# power.net
KiCad netlist of a schematic drawn in Altium Designer
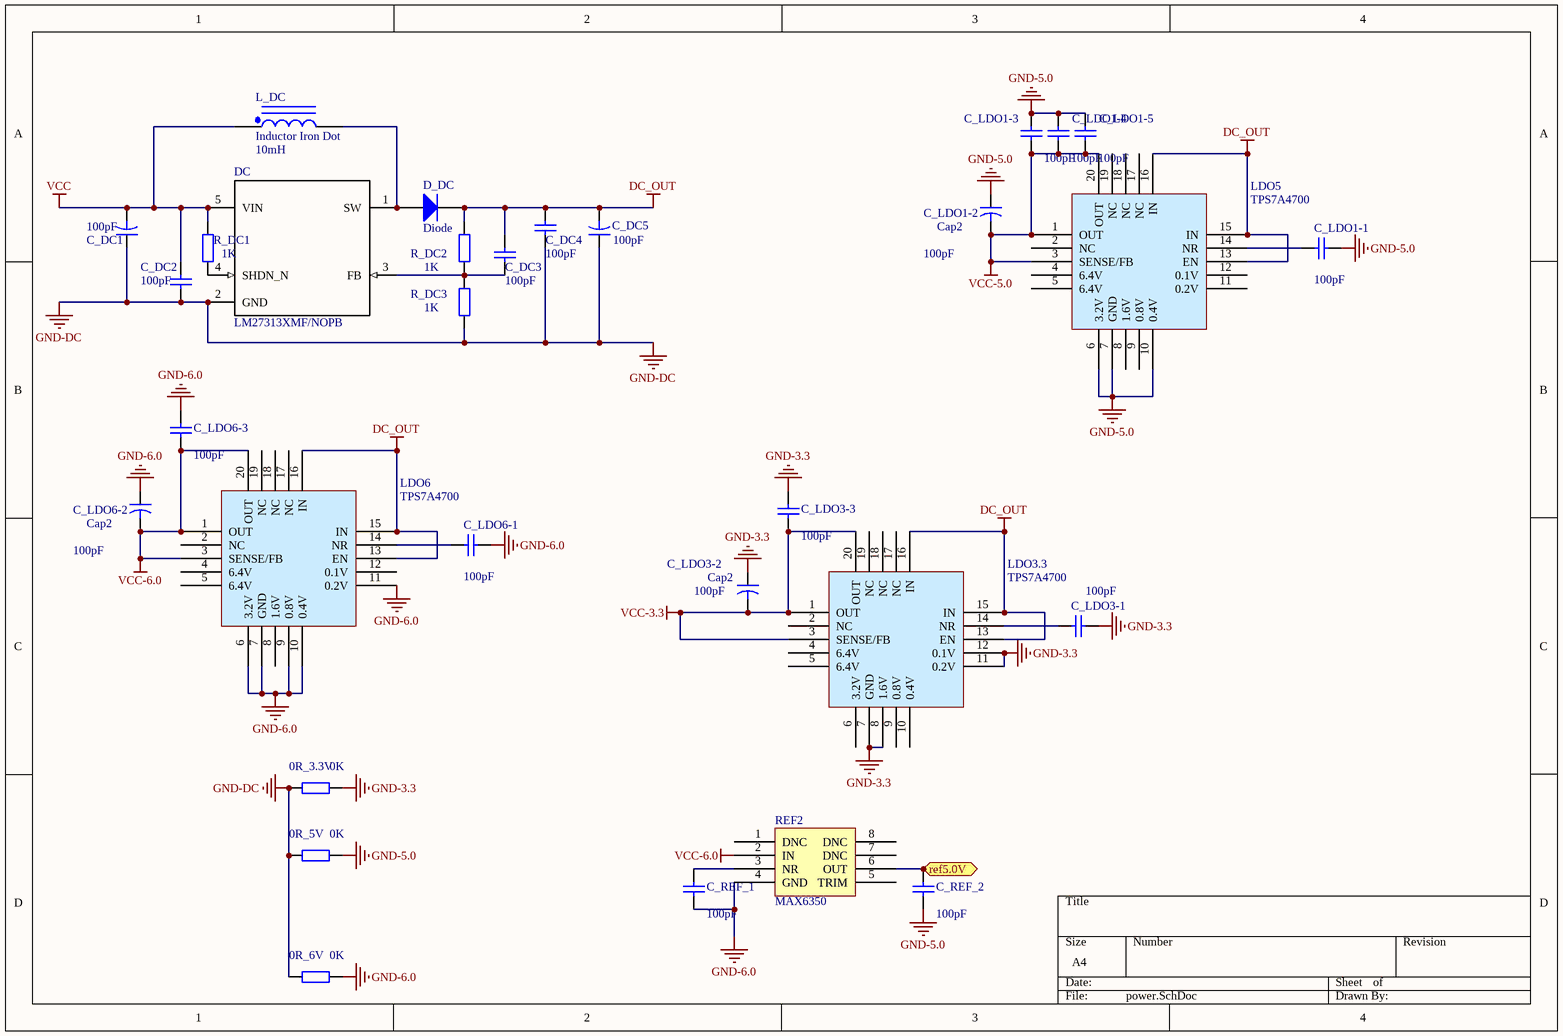
[diagram p0: power.SchDoc]

(export (version "E")
  (design (tool "Eeschema 10.0.6"))
  (components
    (comp (ref "0R_3.3V")
      (value "0K")
      (footprint "0603 - no")
      (description "Resistor")
      (fields (field (name "PUBLISHER") "Altium Limited"))
      (libsource (lib "") (part "Res2_1"))
    )
    (comp (ref "0R_5V")
      (value "0K")
      (footprint "0603 - no")
      (description "Resistor")
      (fields (field (name "PUBLISHER") "Altium Limited"))
      (libsource (lib "") (part "Res2_1"))
    )
    (comp (ref "0R_6V")
      (value "0K")
      (footprint "0603 - no")
      (description "Resistor")
      (fields (field (name "PUBLISHER") "Altium Limited"))
      (libsource (lib "") (part "Res2_1"))
    )
    (comp (ref "C_DC1")
      (value "100pF")
      (footprint "1210")
      (description "Capacitor")
      (fields (field (name "PUBLISHER") "Altium Limited"))
      (libsource (lib "Miscellaneous Devices") (part "Cap2"))
    )
    (comp (ref "C_DC2")
      (value "100pF")
      (footprint "0603 - no")
      (description "Capacitor")
      (fields (field (name "PUBLISHER") "Altium Limited"))
      (libsource (lib "Miscellaneous Devices") (part "Cap"))
    )
    (comp (ref "C_DC3")
      (value "100pF")
      (footprint "0603 - no")
      (description "Capacitor")
      (fields (field (name "PUBLISHER") "Altium Limited"))
      (libsource (lib "Miscellaneous Devices") (part "Cap"))
    )
    (comp (ref "C_DC4")
      (value "100pF")
      (footprint "0805")
      (description "Capacitor")
      (fields (field (name "PUBLISHER") "Altium Limited"))
      (libsource (lib "Miscellaneous Devices") (part "Cap"))
    )
    (comp (ref "C_DC5")
      (value "100pF")
      (footprint "1210")
      (description "Capacitor")
      (fields (field (name "PUBLISHER") "Altium Limited"))
      (libsource (lib "Miscellaneous Devices") (part "Cap2"))
    )
    (comp (ref "C_LDO1-1")
      (value "100pF")
      (footprint "0603 - no")
      (description "Capacitor")
      (fields (field (name "PUBLISHER") "Altium Limited"))
      (libsource (lib "Miscellaneous Devices") (part "Cap"))
    )
    (comp (ref "C_LDO1-2")
      (value "Cap2")
      (footprint "1210")
      (description "Capacitor")
      (fields (field (name "ALTIUM_VALUE") "100pF") (field (name "PUBLISHER") "Altium Limited"))
      (libsource (lib "Miscellaneous Devices") (part "Cap2"))
    )
    (comp (ref "C_LDO1-3")
      (value "100pF")
      (footprint "0805")
      (description "Capacitor")
      (fields (field (name "PUBLISHER") "Altium Limited"))
      (libsource (lib "Miscellaneous Devices") (part "Cap"))
    )
    (comp (ref "C_LDO1-4")
      (value "100pF")
      (footprint "0805")
      (description "Capacitor")
      (fields (field (name "PUBLISHER") "Altium Limited"))
      (libsource (lib "Miscellaneous Devices") (part "Cap"))
    )
    (comp (ref "C_LDO1-5")
      (value "100pF")
      (footprint "0805")
      (description "Capacitor")
      (fields (field (name "PUBLISHER") "Altium Limited"))
      (libsource (lib "Miscellaneous Devices") (part "Cap"))
    )
    (comp (ref "C_LDO3-1")
      (value "100pF")
      (footprint "0603 - no")
      (description "Capacitor")
      (fields (field (name "PUBLISHER") "Altium Limited"))
      (libsource (lib "Miscellaneous Devices") (part "Cap"))
    )
    (comp (ref "C_LDO3-2")
      (value "Cap2")
      (footprint "1210")
      (description "Capacitor")
      (fields (field (name "ALTIUM_VALUE") "100pF") (field (name "PUBLISHER") "Altium Limited"))
      (libsource (lib "Miscellaneous Devices") (part "Cap2"))
    )
    (comp (ref "C_LDO3-3")
      (value "100pF")
      (footprint "0805")
      (description "Capacitor")
      (fields (field (name "PUBLISHER") "Altium Limited"))
      (libsource (lib "Miscellaneous Devices") (part "Cap"))
    )
    (comp (ref "C_LDO6-1")
      (value "100pF")
      (footprint "0603 - no")
      (description "Capacitor")
      (fields (field (name "PUBLISHER") "Altium Limited"))
      (libsource (lib "Miscellaneous Devices") (part "Cap"))
    )
    (comp (ref "C_LDO6-2")
      (value "Cap2")
      (footprint "1210")
      (description "Capacitor")
      (fields (field (name "ALTIUM_VALUE") "100pF") (field (name "PUBLISHER") "Altium Limited"))
      (libsource (lib "Miscellaneous Devices") (part "Cap2"))
    )
    (comp (ref "C_LDO6-3")
      (value "100pF")
      (footprint "0805")
      (description "Capacitor")
      (fields (field (name "PUBLISHER") "Altium Limited"))
      (libsource (lib "Miscellaneous Devices") (part "Cap"))
    )
    (comp (ref "C_REF_1")
      (value "100pF")
      (footprint "0603 - no")
      (description "Capacitor")
      (fields (field (name "PUBLISHER") "Altium Limited"))
      (libsource (lib "Miscellaneous Devices") (part "Cap"))
    )
    (comp (ref "C_REF_2")
      (value "100pF")
      (footprint "0603 - no")
      (description "Capacitor")
      (fields (field (name "PUBLISHER") "Altium Limited"))
      (libsource (lib "Miscellaneous Devices") (part "Cap"))
    )
    (comp (ref "DC")
      (value "LM27313XMF/NOPB")
      (footprint "DBV0005A")
      (description "Imported")
      (fields (field (name "MANUFACTURER") "Texas Instruments"))
      (libsource (lib "complements") (part "LM27313XMF/NOPB"))
    )
    (comp (ref "D_DC")
      (value "Diode")
      (footprint "Diode-SOD123")
      (description "Default Diode")
      (fields (field (name "PUBLISHER") "Altium Limited"))
      (libsource (lib "Miscellaneous Devices") (part "Diode"))
    )
    (comp (ref "LDO3.3")
      (value "TPS7A4700")
      (footprint "TPS7A4700 - b")
      (libsource (lib "complements") (part "TPS7A4700"))
    )
    (comp (ref "LDO5")
      (value "TPS7A4700")
      (footprint "TPS7A4700 - b")
      (libsource (lib "complements") (part "TPS7A4700"))
    )
    (comp (ref "LDO6")
      (value "TPS7A4700")
      (footprint "TPS7A4700 - b")
      (libsource (lib "complements") (part "TPS7A4700"))
    )
    (comp (ref "L_DC")
      (value "Inductor Iron Dot")
      (footprint "GDNR5040")
      (description "Magnetic-Core Inductor with Winding Polarity Marking")
      (fields (field (name "ALTIUM_VALUE") "10mH") (field (name "PUBLISHER") "Altium Limited"))
      (libsource (lib "Miscellaneous Devices") (part "Inductor Iron Dot"))
    )
    (comp (ref "REF2") (value "MAX6350") (footprint "D8") (libsource (lib "complements") (part "MAX6350")))
    (comp (ref "R_DC1")
      (value "1K")
      (footprint "0603 - no")
      (description "Resistor")
      (fields (field (name "PUBLISHER") "Altium Limited"))
      (libsource (lib "Miscellaneous Devices") (part "Res2"))
    )
    (comp (ref "R_DC2")
      (value "1K")
      (footprint "0603 - no")
      (description "Resistor")
      (fields (field (name "PUBLISHER") "Altium Limited"))
      (libsource (lib "Miscellaneous Devices") (part "Res2"))
    )
    (comp (ref "R_DC3")
      (value "1K")
      (footprint "0603 - no")
      (description "Resistor")
      (fields (field (name "PUBLISHER") "Altium Limited"))
      (libsource (lib "Miscellaneous Devices") (part "Res2"))
    )
  )
  (nets
    (net (code "1") (name "/ref5.0V") (class "Default")
      (node (ref "C_REF_2") (pin "1") (pinfunction "1_1") (pintype "passive"))
      (node (ref "REF2") (pin "6") (pinfunction "OUT_6") (pintype "passive"))
    )
    (net (code "2") (name "DC_OUT") (class "Default")
      (node (ref "C_DC3") (pin "2") (pinfunction "2_2") (pintype "passive"))
      (node (ref "C_DC4") (pin "2") (pinfunction "2_2") (pintype "passive"))
      (node (ref "C_DC5") (pin "2") (pinfunction "2_2") (pintype "passive"))
      (node (ref "D_DC") (pin "2") (pinfunction "K_2") (pintype "passive"))
      (node (ref "LDO3.3") (pin "13") (pinfunction "EN_13") (pintype "passive"))
      (node (ref "LDO3.3") (pin "15") (pinfunction "IN_15") (pintype "passive"))
      (node (ref "LDO3.3") (pin "16") (pinfunction "IN_16") (pintype "passive"))
      (node (ref "LDO5") (pin "13") (pinfunction "EN_13") (pintype "passive"))
      (node (ref "LDO5") (pin "15") (pinfunction "IN_15") (pintype "passive"))
      (node (ref "LDO5") (pin "16") (pinfunction "IN_16") (pintype "passive"))
      (node (ref "LDO6") (pin "13") (pinfunction "EN_13") (pintype "passive"))
      (node (ref "LDO6") (pin "15") (pinfunction "IN_15") (pintype "passive"))
      (node (ref "LDO6") (pin "16") (pinfunction "IN_16") (pintype "passive"))
      (node (ref "R_DC2") (pin "2") (pinfunction "2_2") (pintype "passive"))
    )
    (net (code "3") (name "GND-3.3") (class "Default")
      (node (ref "0R_3.3V") (pin "1") (pinfunction "1_1") (pintype "passive"))
      (node (ref "C_LDO3-1") (pin "1") (pinfunction "1_1") (pintype "passive"))
      (node (ref "C_LDO3-2") (pin "1") (pinfunction "1_1") (pintype "passive"))
      (node (ref "C_LDO3-3") (pin "1") (pinfunction "1_1") (pintype "passive"))
      (node (ref "LDO3.3") (pin "11") (pinfunction "0.2V_11") (pintype "passive"))
      (node (ref "LDO3.3") (pin "12") (pinfunction "0.1V_12") (pintype "passive"))
      (node (ref "LDO3.3") (pin "7") (pinfunction "GND_7") (pintype "passive"))
      (node (ref "LDO3.3") (pin "8") (pinfunction "1.6V_8") (pintype "passive"))
    )
    (net (code "4") (name "GND-5.0") (class "Default")
      (node (ref "0R_5V") (pin "1") (pinfunction "1_1") (pintype "passive"))
      (node (ref "C_LDO1-1") (pin "1") (pinfunction "1_1") (pintype "passive"))
      (node (ref "C_LDO1-2") (pin "1") (pinfunction "1_1") (pintype "passive"))
      (node (ref "C_LDO1-3") (pin "1") (pinfunction "1_1") (pintype "passive"))
      (node (ref "C_LDO1-4") (pin "1") (pinfunction "1_1") (pintype "passive"))
      (node (ref "C_LDO1-5") (pin "1") (pinfunction "1_1") (pintype "passive"))
      (node (ref "C_REF_2") (pin "2") (pinfunction "2_2") (pintype "passive"))
      (node (ref "LDO5") (pin "10") (pinfunction "0.4V_10") (pintype "passive"))
      (node (ref "LDO5") (pin "6") (pinfunction "3.2V_6") (pintype "passive"))
      (node (ref "LDO5") (pin "7") (pinfunction "GND_7") (pintype "passive"))
    )
    (net (code "5") (name "GND-6.0") (class "Default")
      (node (ref "0R_6V") (pin "1") (pinfunction "1_1") (pintype "passive"))
      (node (ref "C_LDO6-1") (pin "1") (pinfunction "1_1") (pintype "passive"))
      (node (ref "C_LDO6-2") (pin "1") (pinfunction "1_1") (pintype "passive"))
      (node (ref "C_LDO6-3") (pin "1") (pinfunction "1_1") (pintype "passive"))
      (node (ref "C_REF_1") (pin "2") (pinfunction "2_2") (pintype "passive"))
      (node (ref "LDO6") (pin "10") (pinfunction "0.4V_10") (pintype "passive"))
      (node (ref "LDO6") (pin "11") (pinfunction "0.2V_11") (pintype "passive"))
      (node (ref "LDO6") (pin "6") (pinfunction "3.2V_6") (pintype "passive"))
      (node (ref "LDO6") (pin "7") (pinfunction "GND_7") (pintype "passive"))
      (node (ref "LDO6") (pin "9") (pinfunction "0.8V_9") (pintype "passive"))
      (node (ref "REF2") (pin "4") (pinfunction "GND_4") (pintype "passive"))
    )
    (net (code "6") (name "GND-DC") (class "Default")
      (node (ref "0R_3.3V") (pin "2") (pinfunction "2_2") (pintype "passive"))
      (node (ref "0R_5V") (pin "2") (pinfunction "2_2") (pintype "passive"))
      (node (ref "0R_6V") (pin "2") (pinfunction "2_2") (pintype "passive"))
      (node (ref "C_DC1") (pin "1") (pinfunction "1_1") (pintype "passive"))
      (node (ref "C_DC2") (pin "1") (pinfunction "1_1") (pintype "passive"))
      (node (ref "C_DC4") (pin "1") (pinfunction "1_1") (pintype "passive"))
      (node (ref "C_DC5") (pin "1") (pinfunction "1_1") (pintype "passive"))
      (node (ref "DC") (pin "2") (pinfunction "GND_2") (pintype "power_in"))
      (node (ref "R_DC3") (pin "1") (pinfunction "1_1") (pintype "passive"))
    )
    (net (code "7") (name "Net-(DC-FB)") (class "Default")
      (node (ref "C_DC3") (pin "1") (pinfunction "1_1") (pintype "passive"))
      (node (ref "DC") (pin "3") (pinfunction "FB_3") (pintype "input"))
      (node (ref "R_DC2") (pin "1") (pinfunction "1_1") (pintype "passive"))
      (node (ref "R_DC3") (pin "2") (pinfunction "2_2") (pintype "passive"))
    )
    (net (code "8") (name "Net-(DC-SHDN_N)") (class "Default")
      (node (ref "DC") (pin "4") (pinfunction "SHDN_N_4") (pintype "input"))
      (node (ref "R_DC1") (pin "1") (pinfunction "1_1") (pintype "passive"))
    )
    (net (code "9") (name "Net-(DC-SW)") (class "Default")
      (node (ref "DC") (pin "1") (pinfunction "SW_1") (pintype "power_in"))
      (node (ref "D_DC") (pin "1") (pinfunction "A_1") (pintype "passive"))
      (node (ref "L_DC") (pin "2") (pinfunction "2_2") (pintype "passive"))
    )
    (net (code "10") (name "Net-(LDO3.3-NR)") (class "Default")
      (node (ref "C_LDO3-1") (pin "2") (pinfunction "2_2") (pintype "passive"))
      (node (ref "LDO3.3") (pin "14") (pinfunction "NR_14") (pintype "passive"))
    )
    (net (code "11") (name "Net-(LDO5-NR)") (class "Default")
      (node (ref "C_LDO1-1") (pin "2") (pinfunction "2_2") (pintype "passive"))
      (node (ref "LDO5") (pin "14") (pinfunction "NR_14") (pintype "passive"))
    )
    (net (code "12") (name "Net-(LDO6-NR)") (class "Default")
      (node (ref "C_LDO6-1") (pin "2") (pinfunction "2_2") (pintype "passive"))
      (node (ref "LDO6") (pin "14") (pinfunction "NR_14") (pintype "passive"))
    )
    (net (code "13") (name "Net-(REF2-NR)") (class "Default")
      (node (ref "C_REF_1") (pin "1") (pinfunction "1_1") (pintype "passive"))
      (node (ref "REF2") (pin "3") (pinfunction "NR_3") (pintype "passive"))
    )
    (net (code "14") (name "VCC") (class "Default")
      (node (ref "C_DC1") (pin "2") (pinfunction "2_2") (pintype "passive"))
      (node (ref "C_DC2") (pin "2") (pinfunction "2_2") (pintype "passive"))
      (node (ref "DC") (pin "5") (pinfunction "VIN_5") (pintype "power_in"))
      (node (ref "L_DC") (pin "1") (pinfunction "1_1") (pintype "passive"))
      (node (ref "R_DC1") (pin "2") (pinfunction "2_2") (pintype "passive"))
    )
    (net (code "15") (name "VCC-3.3") (class "Default")
      (node (ref "C_LDO3-2") (pin "2") (pinfunction "2_2") (pintype "passive"))
      (node (ref "C_LDO3-3") (pin "2") (pinfunction "2_2") (pintype "passive"))
      (node (ref "LDO3.3") (pin "1") (pinfunction "OUT_1") (pintype "passive"))
      (node (ref "LDO3.3") (pin "20") (pinfunction "OUT_20") (pintype "passive"))
      (node (ref "LDO3.3") (pin "3") (pinfunction "SENSE/FB_3") (pintype "passive"))
    )
    (net (code "16") (name "VCC-5.0") (class "Default")
      (node (ref "C_LDO1-2") (pin "2") (pinfunction "2_2") (pintype "passive"))
      (node (ref "C_LDO1-3") (pin "2") (pinfunction "2_2") (pintype "passive"))
      (node (ref "C_LDO1-4") (pin "2") (pinfunction "2_2") (pintype "passive"))
      (node (ref "C_LDO1-5") (pin "2") (pinfunction "2_2") (pintype "passive"))
      (node (ref "LDO5") (pin "1") (pinfunction "OUT_1") (pintype "passive"))
      (node (ref "LDO5") (pin "20") (pinfunction "OUT_20") (pintype "passive"))
      (node (ref "LDO5") (pin "3") (pinfunction "SENSE/FB_3") (pintype "passive"))
    )
    (net (code "17") (name "VCC-6.0") (class "Default")
      (node (ref "C_LDO6-2") (pin "2") (pinfunction "2_2") (pintype "passive"))
      (node (ref "C_LDO6-3") (pin "2") (pinfunction "2_2") (pintype "passive"))
      (node (ref "LDO6") (pin "1") (pinfunction "OUT_1") (pintype "passive"))
      (node (ref "LDO6") (pin "20") (pinfunction "OUT_20") (pintype "passive"))
      (node (ref "LDO6") (pin "3") (pinfunction "SENSE/FB_3") (pintype "passive"))
      (node (ref "REF2") (pin "2") (pinfunction "IN_2") (pintype "passive"))
    )
    (net (code "18") (name "unconnected-(LDO3.3-0.4V-Pad10)") (class "Default")
      (node (ref "LDO3.3") (pin "10") (pinfunction "0.4V_10") (pintype "passive"))
    )
    (net (code "19") (name "unconnected-(LDO3.3-0.8V-Pad9)") (class "Default")
      (node (ref "LDO3.3") (pin "9") (pinfunction "0.8V_9") (pintype "passive"))
    )
    (net (code "20") (name "unconnected-(LDO3.3-3.2V-Pad6)") (class "Default")
      (node (ref "LDO3.3") (pin "6") (pinfunction "3.2V_6") (pintype "passive"))
    )
    (net (code "21") (name "unconnected-(LDO3.3-6.4V-Pad4)") (class "Default")
      (node (ref "LDO3.3") (pin "4") (pinfunction "6.4V_4") (pintype "passive"))
    )
    (net (code "22") (name "unconnected-(LDO3.3-6.4V-Pad5)") (class "Default")
      (node (ref "LDO3.3") (pin "5") (pinfunction "6.4V_5") (pintype "passive"))
    )
    (net (code "23") (name "unconnected-(LDO3.3-NC-Pad2)") (class "Default")
      (node (ref "LDO3.3") (pin "2") (pinfunction "NC_2") (pintype "passive"))
    )
    (net (code "24") (name "unconnected-(LDO3.3-NC-Pad17)") (class "Default")
      (node (ref "LDO3.3") (pin "17") (pinfunction "NC_17") (pintype "passive"))
    )
    (net (code "25") (name "unconnected-(LDO3.3-NC-Pad18)") (class "Default")
      (node (ref "LDO3.3") (pin "18") (pinfunction "NC_18") (pintype "passive"))
    )
    (net (code "26") (name "unconnected-(LDO3.3-NC-Pad19)") (class "Default")
      (node (ref "LDO3.3") (pin "19") (pinfunction "NC_19") (pintype "passive"))
    )
    (net (code "27") (name "unconnected-(LDO5-0.1V-Pad12)") (class "Default")
      (node (ref "LDO5") (pin "12") (pinfunction "0.1V_12") (pintype "passive"))
    )
    (net (code "28") (name "unconnected-(LDO5-0.2V-Pad11)") (class "Default")
      (node (ref "LDO5") (pin "11") (pinfunction "0.2V_11") (pintype "passive"))
    )
    (net (code "29") (name "unconnected-(LDO5-0.8V-Pad9)") (class "Default")
      (node (ref "LDO5") (pin "9") (pinfunction "0.8V_9") (pintype "passive"))
    )
    (net (code "30") (name "unconnected-(LDO5-1.6V-Pad8)") (class "Default")
      (node (ref "LDO5") (pin "8") (pinfunction "1.6V_8") (pintype "passive"))
    )
    (net (code "31") (name "unconnected-(LDO5-6.4V-Pad4)") (class "Default")
      (node (ref "LDO5") (pin "4") (pinfunction "6.4V_4") (pintype "passive"))
    )
    (net (code "32") (name "unconnected-(LDO5-6.4V-Pad5)") (class "Default")
      (node (ref "LDO5") (pin "5") (pinfunction "6.4V_5") (pintype "passive"))
    )
    (net (code "33") (name "unconnected-(LDO5-NC-Pad2)") (class "Default")
      (node (ref "LDO5") (pin "2") (pinfunction "NC_2") (pintype "passive"))
    )
    (net (code "34") (name "unconnected-(LDO5-NC-Pad17)") (class "Default")
      (node (ref "LDO5") (pin "17") (pinfunction "NC_17") (pintype "passive"))
    )
    (net (code "35") (name "unconnected-(LDO5-NC-Pad18)") (class "Default")
      (node (ref "LDO5") (pin "18") (pinfunction "NC_18") (pintype "passive"))
    )
    (net (code "36") (name "unconnected-(LDO5-NC-Pad19)") (class "Default")
      (node (ref "LDO5") (pin "19") (pinfunction "NC_19") (pintype "passive"))
    )
    (net (code "37") (name "unconnected-(LDO6-0.1V-Pad12)") (class "Default")
      (node (ref "LDO6") (pin "12") (pinfunction "0.1V_12") (pintype "passive"))
    )
    (net (code "38") (name "unconnected-(LDO6-1.6V-Pad8)") (class "Default")
      (node (ref "LDO6") (pin "8") (pinfunction "1.6V_8") (pintype "passive"))
    )
    (net (code "39") (name "unconnected-(LDO6-6.4V-Pad4)") (class "Default")
      (node (ref "LDO6") (pin "4") (pinfunction "6.4V_4") (pintype "passive"))
    )
    (net (code "40") (name "unconnected-(LDO6-6.4V-Pad5)") (class "Default")
      (node (ref "LDO6") (pin "5") (pinfunction "6.4V_5") (pintype "passive"))
    )
    (net (code "41") (name "unconnected-(LDO6-NC-Pad2)") (class "Default")
      (node (ref "LDO6") (pin "2") (pinfunction "NC_2") (pintype "passive"))
    )
    (net (code "42") (name "unconnected-(LDO6-NC-Pad17)") (class "Default")
      (node (ref "LDO6") (pin "17") (pinfunction "NC_17") (pintype "passive"))
    )
    (net (code "43") (name "unconnected-(LDO6-NC-Pad18)") (class "Default")
      (node (ref "LDO6") (pin "18") (pinfunction "NC_18") (pintype "passive"))
    )
    (net (code "44") (name "unconnected-(LDO6-NC-Pad19)") (class "Default")
      (node (ref "LDO6") (pin "19") (pinfunction "NC_19") (pintype "passive"))
    )
    (net (code "45") (name "unconnected-(REF2-DNC-Pad1)") (class "Default")
      (node (ref "REF2") (pin "1") (pinfunction "DNC_1") (pintype "passive"))
    )
    (net (code "46") (name "unconnected-(REF2-DNC-Pad7)") (class "Default")
      (node (ref "REF2") (pin "7") (pinfunction "DNC_7") (pintype "passive"))
    )
    (net (code "47") (name "unconnected-(REF2-DNC-Pad8)") (class "Default")
      (node (ref "REF2") (pin "8") (pinfunction "DNC_8") (pintype "passive"))
    )
    (net (code "48") (name "unconnected-(REF2-TRIM-Pad5)") (class "Default")
      (node (ref "REF2") (pin "5") (pinfunction "TRIM_5") (pintype "passive"))
    )
  )
)
